# arduino_dojo_shield_rev01.net
KiCad netlist of a schematic drawn in EAGLE
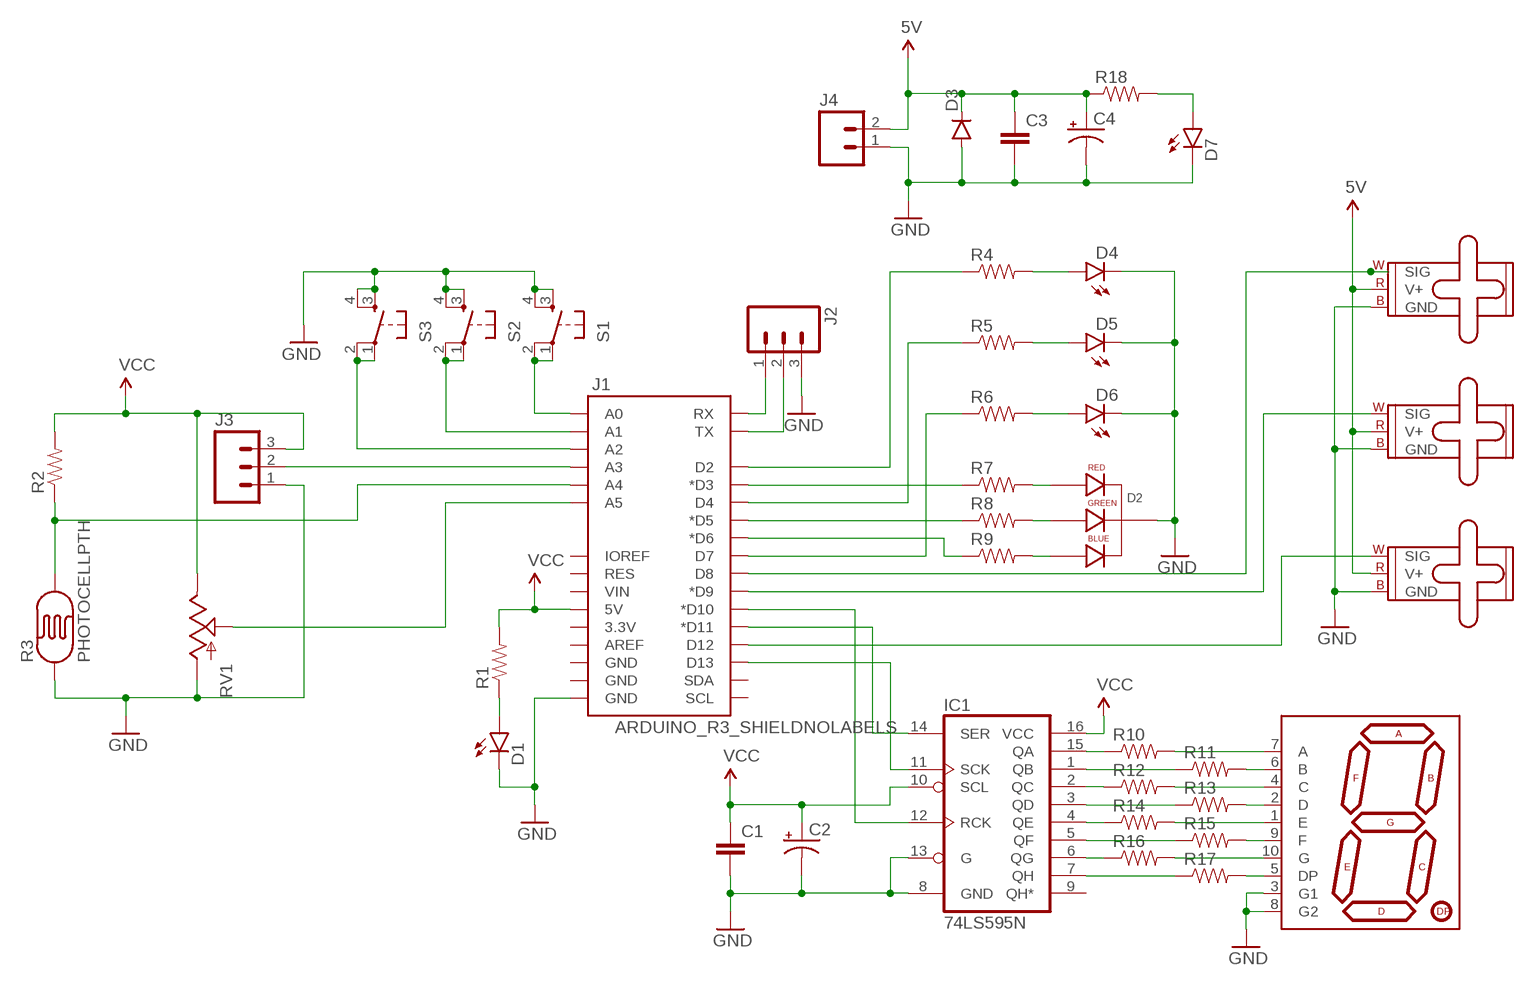
[diagram p0: schematic, sheet 1]

(export (version "E")
  (design (tool "Eeschema 10.0.6"))
  (components
    (comp (ref "C1")
      (value "0.1UF-50V-20%(PTH)KIT-EZ")
      (footprint "eagle-import:CAP-PTH-SMALL-KIT")
      (libsource (lib "eagle-import") (part "0.1UF-50V-20%(PTH)KIT-EZ"))
    )
    (comp (ref "C2")
      (value "10UF-25V-20%(PTH)")
      (footprint "eagle-import:CPOL-RADIAL-10UF-25V")
      (libsource (lib "eagle-import") (part "10UF-25V-20%(PTH)"))
    )
    (comp (ref "C3")
      (value "0.1UF-50V-20%(PTH)KIT-EZ")
      (footprint "eagle-import:CAP-PTH-SMALL-KIT")
      (libsource (lib "eagle-import") (part "0.1UF-50V-20%(PTH)KIT-EZ"))
    )
    (comp (ref "C4")
      (value "10UF-25V-20%(PTH)")
      (footprint "eagle-import:CPOL-RADIAL-10UF-25V")
      (libsource (lib "eagle-import") (part "10UF-25V-20%(PTH)"))
    )
    (comp (ref "D1")
      (value "LED3MM")
      (footprint "eagle-import:LED3MM")
      (libsource (lib "eagle-import") (part "LED3MM"))
    )
    (comp (ref "D2")
      (value "LED-RGB-CC-THRUCLEAR")
      (footprint "eagle-import:LED-RGB-THRU")
      (libsource (lib "eagle-import") (part "LED-RGB-CC-THRUCLEAR"))
    )
    (comp (ref "D3")
      (value "DIODEKIT")
      (footprint "eagle-import:DIODE-1N4148-KIT")
      (libsource (lib "eagle-import") (part "DIODEKIT"))
    )
    (comp (ref "D4")
      (value "LED3MM")
      (footprint "eagle-import:LED3MM")
      (libsource (lib "eagle-import") (part "LED3MM"))
    )
    (comp (ref "D5")
      (value "LED3MM")
      (footprint "eagle-import:LED3MM")
      (libsource (lib "eagle-import") (part "LED3MM"))
    )
    (comp (ref "D6")
      (value "LED3MM")
      (footprint "eagle-import:LED3MM")
      (libsource (lib "eagle-import") (part "LED3MM"))
    )
    (comp (ref "D7")
      (value "LED3MM")
      (footprint "eagle-import:LED3MM")
      (libsource (lib "eagle-import") (part "LED3MM"))
    )
    (comp (ref "IC1")
      (value "74LS595N")
      (footprint "eagle-import:DIL16")
      (libsource (lib "eagle-import") (part "74595NLS"))
    )
    (comp (ref "J1")
      (value "ARDUINO_R3_SHIELDNOLABELS")
      (footprint "eagle-import:UNO_R3_SHIELD_NOLABELS")
      (libsource (lib "eagle-import") (part "ARDUINO_R3_SHIELDNOLABELS"))
    )
    (comp (ref "J2")
      (value "M03PTH")
      (footprint "eagle-import:1X03")
      (libsource (lib "eagle-import") (part "M03PTH"))
    )
    (comp (ref "J3")
      (value "M03PTH")
      (footprint "eagle-import:1X03")
      (libsource (lib "eagle-import") (part "M03PTH"))
    )
    (comp (ref "J4")
      (value "M025MM")
      (footprint "eagle-import:SCREWTERMINAL-5MM-2")
      (libsource (lib "eagle-import") (part "M025MM"))
    )
    (comp (ref "M1")
      (value "SMALL_SERVO")
      (footprint "eagle-import:1X03")
      (libsource (lib "eagle-import") (part "SMALL_SERVO"))
    )
    (comp (ref "M2")
      (value "SMALL_SERVO")
      (footprint "eagle-import:1X03")
      (libsource (lib "eagle-import") (part "SMALL_SERVO"))
    )
    (comp (ref "M3")
      (value "SMALL_SERVO")
      (footprint "eagle-import:1X03")
      (libsource (lib "eagle-import") (part "SMALL_SERVO"))
    )
    (comp (ref "R1")
      (value "RESISTOR0805-RES")
      (footprint "eagle-import:0805")
      (libsource (lib "eagle-import") (part "RESISTOR0805-RES"))
    )
    (comp (ref "R2")
      (value "RESISTORPTH-1/4W")
      (footprint "eagle-import:AXIAL-0.4")
      (libsource (lib "eagle-import") (part "RESISTORPTH-1/4W"))
    )
    (comp (ref "R3")
      (value "PHOTOCELLPTH")
      (footprint "eagle-import:PHOTOCELL")
      (libsource (lib "eagle-import") (part "PHOTOCELLPTH"))
    )
    (comp (ref "R4")
      (value "RESISTOR0805-RES")
      (footprint "eagle-import:0805")
      (libsource (lib "eagle-import") (part "RESISTOR0805-RES"))
    )
    (comp (ref "R5")
      (value "RESISTOR0805-RES")
      (footprint "eagle-import:0805")
      (libsource (lib "eagle-import") (part "RESISTOR0805-RES"))
    )
    (comp (ref "R6")
      (value "RESISTOR0805-RES")
      (footprint "eagle-import:0805")
      (libsource (lib "eagle-import") (part "RESISTOR0805-RES"))
    )
    (comp (ref "R7")
      (value "RESISTOR0805-RES")
      (footprint "eagle-import:0805")
      (libsource (lib "eagle-import") (part "RESISTOR0805-RES"))
    )
    (comp (ref "R8")
      (value "RESISTOR0805-RES")
      (footprint "eagle-import:0805")
      (libsource (lib "eagle-import") (part "RESISTOR0805-RES"))
    )
    (comp (ref "R9")
      (value "RESISTOR0805-RES")
      (footprint "eagle-import:0805")
      (libsource (lib "eagle-import") (part "RESISTOR0805-RES"))
    )
    (comp (ref "R10")
      (value "RESISTOR0805-RES")
      (footprint "eagle-import:0805")
      (libsource (lib "eagle-import") (part "RESISTOR0805-RES"))
    )
    (comp (ref "R11")
      (value "RESISTOR0805-RES")
      (footprint "eagle-import:0805")
      (libsource (lib "eagle-import") (part "RESISTOR0805-RES"))
    )
    (comp (ref "R12")
      (value "RESISTOR0805-RES")
      (footprint "eagle-import:0805")
      (libsource (lib "eagle-import") (part "RESISTOR0805-RES"))
    )
    (comp (ref "R13")
      (value "RESISTOR0805-RES")
      (footprint "eagle-import:0805")
      (libsource (lib "eagle-import") (part "RESISTOR0805-RES"))
    )
    (comp (ref "R14")
      (value "RESISTOR0805-RES")
      (footprint "eagle-import:0805")
      (libsource (lib "eagle-import") (part "RESISTOR0805-RES"))
    )
    (comp (ref "R15")
      (value "RESISTOR0805-RES")
      (footprint "eagle-import:0805")
      (libsource (lib "eagle-import") (part "RESISTOR0805-RES"))
    )
    (comp (ref "R16")
      (value "RESISTOR0805-RES")
      (footprint "eagle-import:0805")
      (libsource (lib "eagle-import") (part "RESISTOR0805-RES"))
    )
    (comp (ref "R17")
      (value "RESISTOR0805-RES")
      (footprint "eagle-import:0805")
      (libsource (lib "eagle-import") (part "RESISTOR0805-RES"))
    )
    (comp (ref "R18")
      (value "RESISTOR0805-RES")
      (footprint "eagle-import:0805")
      (libsource (lib "eagle-import") (part "RESISTOR0805-RES"))
    )
    (comp (ref "RV1")
      (value "POT-RV16AF-20")
      (footprint "eagle-import:POT_ALPHA_RV16AF-20")
      (libsource (lib "eagle-import") (part "POT-RV16AF-20"))
    )
    (comp (ref "S1")
      (value "TAC_SWITCHPTH")
      (footprint "eagle-import:TACTILE-PTH")
      (libsource (lib "eagle-import") (part "TAC_SWITCHPTH"))
    )
    (comp (ref "S2")
      (value "TAC_SWITCHPTH")
      (footprint "eagle-import:TACTILE-PTH")
      (libsource (lib "eagle-import") (part "TAC_SWITCHPTH"))
    )
    (comp (ref "S3")
      (value "TAC_SWITCHPTH")
      (footprint "eagle-import:TACTILE-PTH")
      (libsource (lib "eagle-import") (part "TAC_SWITCHPTH"))
    )
    (comp (ref "U$1")
      (value "7-SEGMENT-DISPLAYPTH")
      (footprint "eagle-import:7-SEGMENT-DISPLAY")
      (libsource (lib "eagle-import") (part "7-SEGMENT-DISPLAYPTH"))
    )
  )
  (nets
    (net (code "1") (name "5V") (class "Default")
      (node (ref "C3") (pin "1") (pinfunction "1_1") (pintype "passive"))
      (node (ref "C4") (pin "1") (pinfunction "+_1") (pintype "passive"))
      (node (ref "D3") (pin "C") (pinfunction "C_C") (pintype "passive"))
      (node (ref "J4") (pin "2") (pinfunction "2_2") (pintype "passive"))
      (node (ref "M1") (pin "2") (pinfunction "V+_2") (pintype "bidirectional"))
      (node (ref "M2") (pin "2") (pinfunction "V+_2") (pintype "bidirectional"))
      (node (ref "M3") (pin "2") (pinfunction "V+_2") (pintype "bidirectional"))
      (node (ref "R18") (pin "1") (pinfunction "1_1") (pintype "passive"))
    )
    (net (code "2") (name "GND") (class "Default")
      (node (ref "C1") (pin "2") (pinfunction "2_2") (pintype "passive"))
      (node (ref "C2") (pin "2") (pinfunction "-_2") (pintype "passive"))
      (node (ref "C3") (pin "2") (pinfunction "2_2") (pintype "passive"))
      (node (ref "C4") (pin "2") (pinfunction "-_2") (pintype "passive"))
      (node (ref "D1") (pin "K") (pinfunction "C_K") (pintype "passive"))
      (node (ref "D2") (pin "2") (pinfunction "CATHODE_2") (pintype "bidirectional"))
      (node (ref "D3") (pin "A") (pinfunction "A_A") (pintype "passive"))
      (node (ref "D4") (pin "K") (pinfunction "C_K") (pintype "passive"))
      (node (ref "D5") (pin "K") (pinfunction "C_K") (pintype "passive"))
      (node (ref "D6") (pin "K") (pinfunction "C_K") (pintype "passive"))
      (node (ref "D7") (pin "K") (pinfunction "C_K") (pintype "passive"))
      (node (ref "IC1") (pin "13") (pinfunction "G_13") (pintype "input"))
      (node (ref "IC1") (pin "8") (pinfunction "GND_8") (pintype "power_in"))
      (node (ref "J1") (pin "GND@0") (pinfunction "GND_GND@0") (pintype "bidirectional"))
      (node (ref "J2") (pin "3") (pinfunction "3_3") (pintype "passive"))
      (node (ref "J3") (pin "1") (pinfunction "1_1") (pintype "passive"))
      (node (ref "J4") (pin "1") (pinfunction "1_1") (pintype "passive"))
      (node (ref "M1") (pin "3") (pinfunction "GND_3") (pintype "bidirectional"))
      (node (ref "M2") (pin "3") (pinfunction "GND_3") (pintype "bidirectional"))
      (node (ref "M3") (pin "3") (pinfunction "GND_3") (pintype "bidirectional"))
      (node (ref "R3") (pin "1") (pinfunction "P$1_1") (pintype "bidirectional"))
      (node (ref "RV1") (pin "1") (pinfunction "A_1") (pintype "passive"))
      (node (ref "S1") (pin "3") (pinfunction "3_3") (pintype "passive"))
      (node (ref "S1") (pin "4") (pinfunction "4_4") (pintype "passive"))
      (node (ref "S2") (pin "3") (pinfunction "3_3") (pintype "passive"))
      (node (ref "S2") (pin "4") (pinfunction "4_4") (pintype "passive"))
      (node (ref "S3") (pin "3") (pinfunction "3_3") (pintype "passive"))
      (node (ref "S3") (pin "4") (pinfunction "4_4") (pintype "passive"))
      (node (ref "U$1") (pin "3") (pinfunction "G1_3") (pintype "bidirectional"))
      (node (ref "U$1") (pin "8") (pinfunction "G2_8") (pintype "bidirectional"))
    )
    (net (code "3") (name "Net-(D1-PadA)") (class "Default")
      (node (ref "D1") (pin "A") (pinfunction "A_A") (pintype "passive"))
      (node (ref "R1") (pin "1") (pinfunction "1_1") (pintype "passive"))
    )
    (net (code "4") (name "Net-(D2-BLUE_CATHODE)") (class "Default")
      (node (ref "D2") (pin "4") (pinfunction "BLUE_CATHODE_4") (pintype "bidirectional"))
      (node (ref "R9") (pin "2") (pinfunction "2_2") (pintype "passive"))
    )
    (net (code "5") (name "Net-(D2-GREEN_CATHODE)") (class "Default")
      (node (ref "D2") (pin "3") (pinfunction "GREEN_CATHODE_3") (pintype "bidirectional"))
      (node (ref "R8") (pin "2") (pinfunction "2_2") (pintype "passive"))
    )
    (net (code "6") (name "Net-(D2-RED_CATHODE)") (class "Default")
      (node (ref "D2") (pin "1") (pinfunction "RED_CATHODE_1") (pintype "bidirectional"))
      (node (ref "R7") (pin "2") (pinfunction "2_2") (pintype "passive"))
    )
    (net (code "7") (name "Net-(D4-PadA)") (class "Default")
      (node (ref "D4") (pin "A") (pinfunction "A_A") (pintype "passive"))
      (node (ref "R4") (pin "2") (pinfunction "2_2") (pintype "passive"))
    )
    (net (code "8") (name "Net-(D5-PadA)") (class "Default")
      (node (ref "D5") (pin "A") (pinfunction "A_A") (pintype "passive"))
      (node (ref "R5") (pin "2") (pinfunction "2_2") (pintype "passive"))
    )
    (net (code "9") (name "Net-(D6-PadA)") (class "Default")
      (node (ref "D6") (pin "A") (pinfunction "A_A") (pintype "passive"))
      (node (ref "R6") (pin "2") (pinfunction "2_2") (pintype "passive"))
    )
    (net (code "10") (name "Net-(D7-PadA)") (class "Default")
      (node (ref "D7") (pin "A") (pinfunction "A_A") (pintype "passive"))
      (node (ref "R18") (pin "2") (pinfunction "2_2") (pintype "passive"))
    )
    (net (code "11") (name "Net-(IC1-QA)") (class "Default")
      (node (ref "IC1") (pin "15") (pinfunction "QA_15") (pintype "tri_state"))
      (node (ref "R10") (pin "1") (pinfunction "1_1") (pintype "passive"))
    )
    (net (code "12") (name "Net-(IC1-QB)") (class "Default")
      (node (ref "IC1") (pin "1") (pinfunction "QB_1") (pintype "tri_state"))
      (node (ref "R11") (pin "1") (pinfunction "1_1") (pintype "passive"))
    )
    (net (code "13") (name "Net-(IC1-QC)") (class "Default")
      (node (ref "IC1") (pin "2") (pinfunction "QC_2") (pintype "tri_state"))
      (node (ref "R12") (pin "1") (pinfunction "1_1") (pintype "passive"))
    )
    (net (code "14") (name "Net-(IC1-QD)") (class "Default")
      (node (ref "IC1") (pin "3") (pinfunction "QD_3") (pintype "tri_state"))
      (node (ref "R13") (pin "1") (pinfunction "1_1") (pintype "passive"))
    )
    (net (code "15") (name "Net-(IC1-QE)") (class "Default")
      (node (ref "IC1") (pin "4") (pinfunction "QE_4") (pintype "tri_state"))
      (node (ref "R14") (pin "1") (pinfunction "1_1") (pintype "passive"))
    )
    (net (code "16") (name "Net-(IC1-QF)") (class "Default")
      (node (ref "IC1") (pin "5") (pinfunction "QF_5") (pintype "tri_state"))
      (node (ref "R15") (pin "1") (pinfunction "1_1") (pintype "passive"))
    )
    (net (code "17") (name "Net-(IC1-QG)") (class "Default")
      (node (ref "IC1") (pin "6") (pinfunction "QG_6") (pintype "tri_state"))
      (node (ref "R16") (pin "1") (pinfunction "1_1") (pintype "passive"))
    )
    (net (code "18") (name "Net-(IC1-QH)") (class "Default")
      (node (ref "IC1") (pin "7") (pinfunction "QH_7") (pintype "tri_state"))
      (node (ref "R17") (pin "1") (pinfunction "1_1") (pintype "passive"))
    )
    (net (code "19") (name "Net-(IC1-RCK)") (class "Default")
      (node (ref "IC1") (pin "12") (pinfunction "RCK_12") (pintype "input"))
      (node (ref "J1") (pin "D10") (pinfunction "*D10_D10") (pintype "bidirectional"))
    )
    (net (code "20") (name "Net-(IC1-SCK)") (class "Default")
      (node (ref "IC1") (pin "11") (pinfunction "SCK_11") (pintype "input"))
      (node (ref "J1") (pin "D13") (pinfunction "D13_D13") (pintype "bidirectional"))
    )
    (net (code "21") (name "Net-(IC1-SER)") (class "Default")
      (node (ref "IC1") (pin "14") (pinfunction "SER_14") (pintype "input"))
      (node (ref "J1") (pin "D11") (pinfunction "*D11_D11") (pintype "bidirectional"))
    )
    (net (code "22") (name "Net-(J1-*D3)") (class "Default")
      (node (ref "J1") (pin "D3") (pinfunction "*D3_D3") (pintype "bidirectional"))
      (node (ref "R7") (pin "1") (pinfunction "1_1") (pintype "passive"))
    )
    (net (code "23") (name "Net-(J1-*D5)") (class "Default")
      (node (ref "J1") (pin "D5") (pinfunction "*D5_D5") (pintype "bidirectional"))
      (node (ref "R8") (pin "1") (pinfunction "1_1") (pintype "passive"))
    )
    (net (code "24") (name "Net-(J1-*D6)") (class "Default")
      (node (ref "J1") (pin "D6") (pinfunction "*D6_D6") (pintype "bidirectional"))
      (node (ref "R9") (pin "1") (pinfunction "1_1") (pintype "passive"))
    )
    (net (code "25") (name "Net-(J1-*D9)") (class "Default")
      (node (ref "J1") (pin "D9") (pinfunction "*D9_D9") (pintype "bidirectional"))
      (node (ref "M1") (pin "1") (pinfunction "SIG_1") (pintype "bidirectional"))
    )
    (net (code "26") (name "Net-(J1-PadA0)") (class "Default")
      (node (ref "J1") (pin "A0") (pinfunction "A0_A0") (pintype "bidirectional"))
      (node (ref "S1") (pin "1") (pinfunction "1_1") (pintype "passive"))
      (node (ref "S1") (pin "2") (pinfunction "2_2") (pintype "passive"))
    )
    (net (code "27") (name "Net-(J1-PadA1)") (class "Default")
      (node (ref "J1") (pin "A1") (pinfunction "A1_A1") (pintype "bidirectional"))
      (node (ref "S2") (pin "1") (pinfunction "1_1") (pintype "passive"))
      (node (ref "S2") (pin "2") (pinfunction "2_2") (pintype "passive"))
    )
    (net (code "28") (name "Net-(J1-PadA2)") (class "Default")
      (node (ref "J1") (pin "A2") (pinfunction "A2_A2") (pintype "bidirectional"))
      (node (ref "S3") (pin "1") (pinfunction "1_1") (pintype "passive"))
      (node (ref "S3") (pin "2") (pinfunction "2_2") (pintype "passive"))
    )
    (net (code "29") (name "Net-(J1-PadA3)") (class "Default")
      (node (ref "J1") (pin "A3") (pinfunction "A3_A3") (pintype "bidirectional"))
      (node (ref "J3") (pin "2") (pinfunction "2_2") (pintype "passive"))
    )
    (net (code "30") (name "Net-(J1-PadD2)") (class "Default")
      (node (ref "J1") (pin "D2") (pinfunction "D2_D2") (pintype "bidirectional"))
      (node (ref "R4") (pin "1") (pinfunction "1_1") (pintype "passive"))
    )
    (net (code "31") (name "Net-(J1-PadD4)") (class "Default")
      (node (ref "J1") (pin "D4") (pinfunction "D4_D4") (pintype "bidirectional"))
      (node (ref "R5") (pin "1") (pinfunction "1_1") (pintype "passive"))
    )
    (net (code "32") (name "Net-(J1-PadD7)") (class "Default")
      (node (ref "J1") (pin "D7") (pinfunction "D7_D7") (pintype "bidirectional"))
      (node (ref "R6") (pin "1") (pinfunction "1_1") (pintype "passive"))
    )
    (net (code "33") (name "Net-(J1-PadRX)") (class "Default")
      (node (ref "J1") (pin "RX") (pinfunction "RX_RX") (pintype "bidirectional"))
      (node (ref "J2") (pin "1") (pinfunction "1_1") (pintype "passive"))
    )
    (net (code "34") (name "Net-(J1-PadTX)") (class "Default")
      (node (ref "J1") (pin "TX") (pinfunction "TX_TX") (pintype "bidirectional"))
      (node (ref "J2") (pin "2") (pinfunction "2_2") (pintype "passive"))
    )
    (net (code "35") (name "Net-(M2-SIG)") (class "Default")
      (node (ref "J1") (pin "D12") (pinfunction "D12_D12") (pintype "bidirectional"))
      (node (ref "M2") (pin "1") (pinfunction "SIG_1") (pintype "bidirectional"))
    )
    (net (code "36") (name "Net-(M3-SIG)") (class "Default")
      (node (ref "J1") (pin "D8") (pinfunction "D8_D8") (pintype "bidirectional"))
      (node (ref "M3") (pin "1") (pinfunction "SIG_1") (pintype "bidirectional"))
    )
    (net (code "37") (name "Net-(R2-1)") (class "Default")
      (node (ref "J1") (pin "A4") (pinfunction "A4_A4") (pintype "bidirectional"))
      (node (ref "R2") (pin "P$1") (pinfunction "1_P$1") (pintype "passive"))
      (node (ref "R3") (pin "2") (pinfunction "P$2_2") (pintype "bidirectional"))
    )
    (net (code "38") (name "Net-(RV1-S)") (class "Default")
      (node (ref "J1") (pin "A5") (pinfunction "A5_A5") (pintype "bidirectional"))
      (node (ref "RV1") (pin "2") (pinfunction "S_2") (pintype "passive"))
    )
    (net (code "39") (name "Net-(U$1-A)") (class "Default")
      (node (ref "R10") (pin "2") (pinfunction "2_2") (pintype "passive"))
      (node (ref "U$1") (pin "7") (pinfunction "A_7") (pintype "bidirectional"))
    )
    (net (code "40") (name "Net-(U$1-B)") (class "Default")
      (node (ref "R11") (pin "2") (pinfunction "2_2") (pintype "passive"))
      (node (ref "U$1") (pin "6") (pinfunction "B_6") (pintype "bidirectional"))
    )
    (net (code "41") (name "Net-(U$1-C)") (class "Default")
      (node (ref "R12") (pin "2") (pinfunction "2_2") (pintype "passive"))
      (node (ref "U$1") (pin "4") (pinfunction "C_4") (pintype "bidirectional"))
    )
    (net (code "42") (name "Net-(U$1-D)") (class "Default")
      (node (ref "R13") (pin "2") (pinfunction "2_2") (pintype "passive"))
      (node (ref "U$1") (pin "2") (pinfunction "D_2") (pintype "bidirectional"))
    )
    (net (code "43") (name "Net-(U$1-DP)") (class "Default")
      (node (ref "R17") (pin "2") (pinfunction "2_2") (pintype "passive"))
      (node (ref "U$1") (pin "5") (pinfunction "DP_5") (pintype "bidirectional"))
    )
    (net (code "44") (name "Net-(U$1-E)") (class "Default")
      (node (ref "R14") (pin "2") (pinfunction "2_2") (pintype "passive"))
      (node (ref "U$1") (pin "1") (pinfunction "E_1") (pintype "bidirectional"))
    )
    (net (code "45") (name "Net-(U$1-F)") (class "Default")
      (node (ref "R15") (pin "2") (pinfunction "2_2") (pintype "passive"))
      (node (ref "U$1") (pin "9") (pinfunction "F_9") (pintype "bidirectional"))
    )
    (net (code "46") (name "Net-(U$1-G)") (class "Default")
      (node (ref "R16") (pin "2") (pinfunction "2_2") (pintype "passive"))
      (node (ref "U$1") (pin "10") (pinfunction "G_10") (pintype "bidirectional"))
    )
    (net (code "47") (name "VCC") (class "Default")
      (node (ref "C1") (pin "1") (pinfunction "1_1") (pintype "passive"))
      (node (ref "C2") (pin "1") (pinfunction "+_1") (pintype "passive"))
      (node (ref "IC1") (pin "10") (pinfunction "SCL_10") (pintype "input"))
      (node (ref "IC1") (pin "16") (pinfunction "VCC_16") (pintype "power_in"))
      (node (ref "J1") (pin "5V") (pinfunction "5V_5V") (pintype "bidirectional"))
      (node (ref "J3") (pin "3") (pinfunction "3_3") (pintype "passive"))
      (node (ref "R1") (pin "2") (pinfunction "2_2") (pintype "passive"))
      (node (ref "R2") (pin "P$2") (pinfunction "2_P$2") (pintype "passive"))
      (node (ref "RV1") (pin "3") (pinfunction "E_3") (pintype "passive"))
    )
    (net (code "48") (name "unconnected-(IC1-QH*-Pad9)") (class "Default")
      (node (ref "IC1") (pin "9") (pinfunction "QH*_9") (pintype "tri_state"))
    )
    (net (code "49") (name "unconnected-(J1-GND-PadGND@1)") (class "Default")
      (node (ref "J1") (pin "GND@1") (pinfunction "GND_GND@1") (pintype "bidirectional"))
    )
    (net (code "50") (name "unconnected-(J1-GND-PadGND@2)") (class "Default")
      (node (ref "J1") (pin "GND@2") (pinfunction "GND_GND@2") (pintype "bidirectional"))
    )
    (net (code "51") (name "unconnected-(J1-Pad3.3V)") (class "Default")
      (node (ref "J1") (pin "3.3V") (pinfunction "3.3V_3.3V") (pintype "bidirectional"))
    )
    (net (code "52") (name "unconnected-(J1-PadAREF)") (class "Default")
      (node (ref "J1") (pin "AREF") (pinfunction "AREF_AREF") (pintype "bidirectional"))
    )
    (net (code "53") (name "unconnected-(J1-PadIOREF)") (class "Default")
      (node (ref "J1") (pin "IOREF") (pinfunction "IOREF_IOREF") (pintype "bidirectional"))
    )
    (net (code "54") (name "unconnected-(J1-PadRES)") (class "Default")
      (node (ref "J1") (pin "RES") (pinfunction "RES_RES") (pintype "bidirectional"))
    )
    (net (code "55") (name "unconnected-(J1-PadSCL)") (class "Default")
      (node (ref "J1") (pin "SCL") (pinfunction "SCL_SCL") (pintype "bidirectional"))
    )
    (net (code "56") (name "unconnected-(J1-PadSDA)") (class "Default")
      (node (ref "J1") (pin "SDA") (pinfunction "SDA_SDA") (pintype "bidirectional"))
    )
    (net (code "57") (name "unconnected-(J1-PadVIN)") (class "Default")
      (node (ref "J1") (pin "VIN") (pinfunction "VIN_VIN") (pintype "bidirectional"))
    )
  )
)
